# Yukari_3_11DoF_2.net
KiCad netlist of a schematic drawn in EAGLE
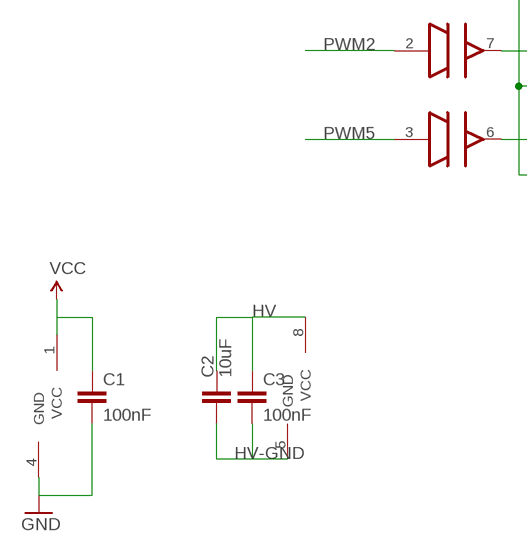
[diagram p0: schematic, sheet 1, part 1 of 2]
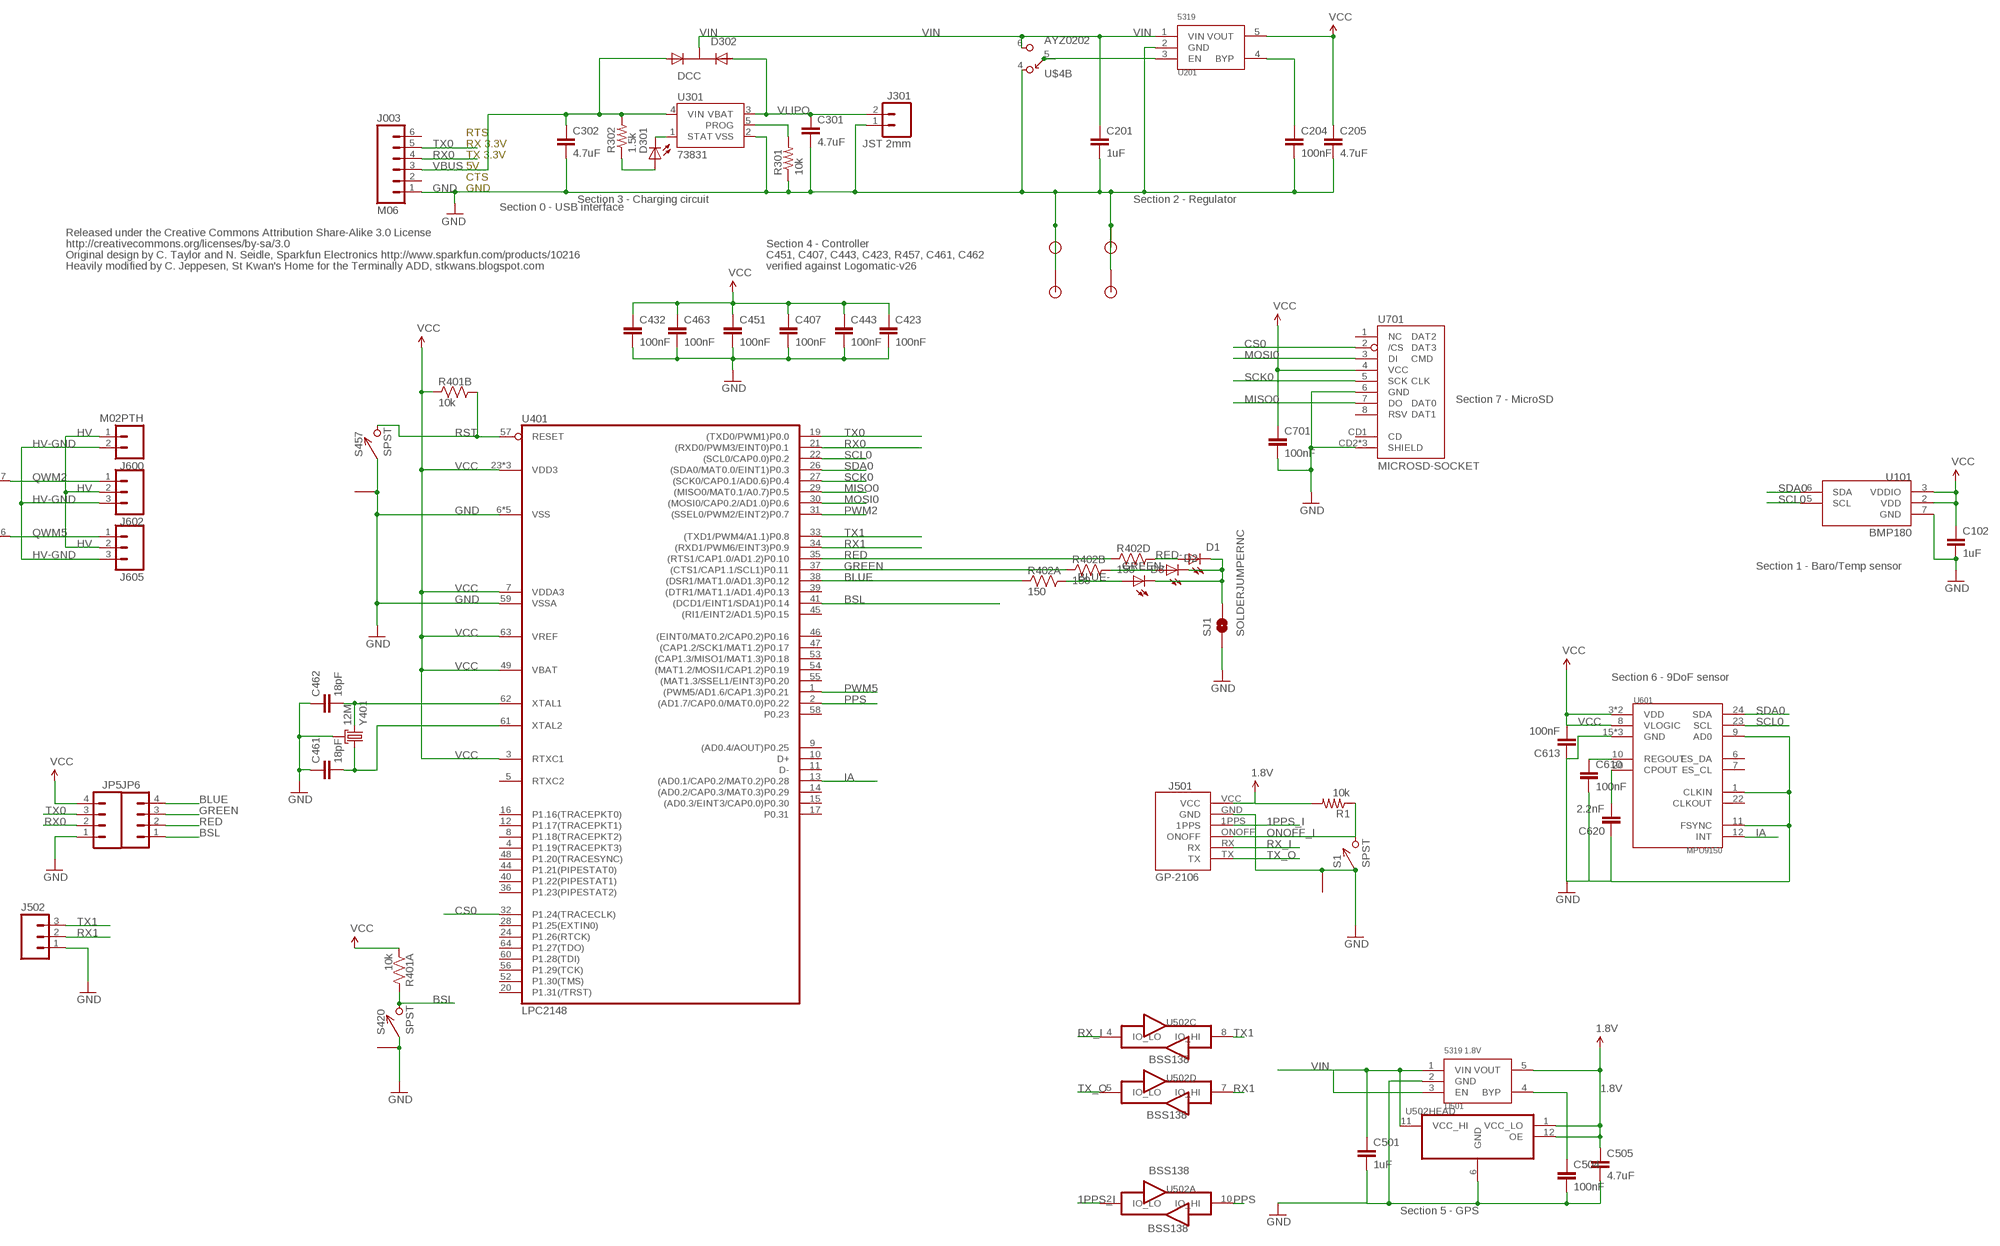
[diagram p1: schematic, sheet 1, part 2 of 2]

(export (version "E")
  (design (tool "Eeschema 10.0.6"))
  (components
    (comp (ref "C1")
      (value "100nF")
      (footprint "eagle-import:0402-CAP")
      (libsource (lib "eagle-import") (part "CAP0402-CAP"))
    )
    (comp (ref "C2")
      (value "10uF")
      (footprint "eagle-import:0603-CAP")
      (libsource (lib "eagle-import") (part "CAP0603-CAP"))
    )
    (comp (ref "C3")
      (value "100nF")
      (footprint "eagle-import:0402-CAP")
      (libsource (lib "eagle-import") (part "CAP0402-CAP"))
    )
    (comp (ref "C102")
      (value "1uF")
      (footprint "eagle-import:0402-CAP")
      (libsource (lib "eagle-import") (part "SparkFun-Passives_CAP0402-CAP"))
    )
    (comp (ref "C201")
      (value "1uF")
      (footprint "eagle-import:0402-CAP")
      (libsource (lib "eagle-import") (part "CAP0402-CAP"))
    )
    (comp (ref "C204")
      (value "100nF")
      (footprint "eagle-import:0402-CAP")
      (libsource (lib "eagle-import") (part "CAP0402-CAP"))
    )
    (comp (ref "C205")
      (value "4.7uF")
      (footprint "eagle-import:0402-CAP")
      (libsource (lib "eagle-import") (part "CAP0402-CAP"))
    )
    (comp (ref "C301")
      (value "4.7uF")
      (footprint "eagle-import:0402-CAP")
      (libsource (lib "eagle-import") (part "CAP0402-CAP"))
    )
    (comp (ref "C302")
      (value "4.7uF")
      (footprint "eagle-import:0402-CAP")
      (libsource (lib "eagle-import") (part "CAP0402-CAP"))
    )
    (comp (ref "C407")
      (value "100nF")
      (footprint "eagle-import:0402-CAP")
      (libsource (lib "eagle-import") (part "CAP0402-CAP"))
    )
    (comp (ref "C423")
      (value "100nF")
      (footprint "eagle-import:0402-CAP")
      (libsource (lib "eagle-import") (part "CAP0402-CAP"))
    )
    (comp (ref "C432")
      (value "100nF")
      (footprint "eagle-import:0402-CAP")
      (libsource (lib "eagle-import") (part "CAP0402-CAP"))
    )
    (comp (ref "C443")
      (value "100nF")
      (footprint "eagle-import:0402-CAP")
      (libsource (lib "eagle-import") (part "CAP0402-CAP"))
    )
    (comp (ref "C451")
      (value "100nF")
      (footprint "eagle-import:0402-CAP")
      (libsource (lib "eagle-import") (part "CAP0402-CAP"))
    )
    (comp (ref "C461")
      (value "18pF")
      (footprint "eagle-import:0402-CAP")
      (libsource (lib "eagle-import") (part "CAP0402-CAP"))
    )
    (comp (ref "C462")
      (value "18pF")
      (footprint "eagle-import:0402-CAP")
      (libsource (lib "eagle-import") (part "CAP0402-CAP"))
    )
    (comp (ref "C463")
      (value "100nF")
      (footprint "eagle-import:0402-CAP")
      (libsource (lib "eagle-import") (part "CAP0402-CAP"))
    )
    (comp (ref "C501")
      (value "1uF")
      (footprint "eagle-import:0402-CAP")
      (libsource (lib "eagle-import") (part "CAP0402-CAP"))
    )
    (comp (ref "C504")
      (value "100nF")
      (footprint "eagle-import:0402-CAP")
      (libsource (lib "eagle-import") (part "CAP0402-CAP"))
    )
    (comp (ref "C505")
      (value "4.7uF")
      (footprint "eagle-import:0402-CAP")
      (libsource (lib "eagle-import") (part "CAP0402-CAP"))
    )
    (comp (ref "C610")
      (value "100nF")
      (footprint "eagle-import:0402-CAP")
      (libsource (lib "eagle-import") (part "SparkFun-Passives_CAP0402-CAP"))
    )
    (comp (ref "C613")
      (value "100nF")
      (footprint "eagle-import:0402-CAP")
      (libsource (lib "eagle-import") (part "SparkFun-Passives_CAP0402-CAP"))
    )
    (comp (ref "C620")
      (value "2.2nF")
      (footprint "eagle-import:0402-CAP")
      (libsource (lib "eagle-import") (part "SparkFun-Passives_CAP0402-CAP"))
    )
    (comp (ref "C701")
      (value "100nF")
      (footprint "eagle-import:0402-CAP")
      (libsource (lib "eagle-import") (part "CAP0402-CAP"))
    )
    (comp (ref "D1")
      (value "RED")
      (footprint "eagle-import:LED-0603")
      (libsource (lib "eagle-import") (part "LED0603"))
    )
    (comp (ref "D2")
      (value "GREEN")
      (footprint "eagle-import:LED-0603")
      (libsource (lib "eagle-import") (part "LED0603"))
    )
    (comp (ref "D3")
      (value "BLUE")
      (footprint "eagle-import:LED-0603")
      (libsource (lib "eagle-import") (part "LED0603"))
    )
    (comp (ref "D301")
      (value "RED")
      (footprint "eagle-import:LED-0603")
      (libsource (lib "eagle-import") (part "LED0603"))
    )
    (comp (ref "D302")
      (value "DCC")
      (footprint "eagle-import:SOT-23-3")
      (libsource (lib "eagle-import") (part "PMEG2005CT"))
    )
    (comp (ref "J003")
      (value "M06")
      (footprint "eagle-import:1X06")
      (libsource (lib "eagle-import") (part "M06SIP"))
    )
    (comp (ref "J301")
      (value "JST 2mm")
      (footprint "eagle-import:JST-2-SMD")
      (libsource (lib "eagle-import") (part "M02-JST-2MM-SMT"))
    )
    (comp (ref "J501")
      (value "GP-2106")
      (footprint "eagle-import:GP-2106")
      (libsource (lib "eagle-import") (part "GP-2106"))
    )
    (comp (ref "J502")
      (value "M03PTH")
      (footprint "eagle-import:1X03")
      (libsource (lib "eagle-import") (part "M03PTH"))
    )
    (comp (ref "J600")
      (value "M02PTH")
      (footprint "eagle-import:1X02")
      (libsource (lib "eagle-import") (part "SparkFun-Connectors_M02PTH"))
    )
    (comp (ref "J602")
      (value "M03PTH")
      (footprint "eagle-import:1X03")
      (libsource (lib "eagle-import") (part "M03PTH"))
    )
    (comp (ref "J605")
      (value "M03PTH")
      (footprint "eagle-import:1X03")
      (libsource (lib "eagle-import") (part "M03PTH"))
    )
    (comp (ref "JP1")
      (value "STANDOFF")
      (footprint "eagle-import:STANDOFF")
      (libsource (lib "eagle-import") (part "STANDOFF"))
    )
    (comp (ref "JP2")
      (value "STANDOFF")
      (footprint "eagle-import:STANDOFF")
      (libsource (lib "eagle-import") (part "STANDOFF"))
    )
    (comp (ref "JP3")
      (value "STANDOFF")
      (footprint "eagle-import:STANDOFF")
      (libsource (lib "eagle-import") (part "STANDOFF"))
    )
    (comp (ref "JP4")
      (value "STANDOFF")
      (footprint "eagle-import:STANDOFF")
      (libsource (lib "eagle-import") (part "STANDOFF"))
    )
    (comp (ref "JP5")
      (value "M04PTH")
      (footprint "eagle-import:1X04")
      (libsource (lib "eagle-import") (part "M04PTH"))
    )
    (comp (ref "JP6")
      (value "M04PTH")
      (footprint "eagle-import:1X04")
      (libsource (lib "eagle-import") (part "M04PTH"))
    )
    (comp (ref "R1")
      (value "10k")
      (footprint "eagle-import:0402-RES")
      (libsource (lib "eagle-import") (part "RESISTOR0402-RES"))
    )
    (comp (ref "R301")
      (value "10k")
      (footprint "eagle-import:0402-RES")
      (libsource (lib "eagle-import") (part "RESISTOR0402-RES"))
    )
    (comp (ref "R302")
      (value "1.5k")
      (footprint "eagle-import:0402-RES")
      (libsource (lib "eagle-import") (part "RESISTOR0402-RES"))
    )
    (comp (ref "R401")
      (value "10k")
      (footprint "eagle-import:CRA02")
      (libsource (lib "eagle-import") (part "RP2EXB24V"))
    )
    (comp (ref "R402")
      (value "150")
      (footprint "eagle-import:CRA04")
      (libsource (lib "eagle-import") (part "RP404"))
    )
    (comp (ref "S1")
      (value "SPST")
      (footprint "eagle-import:B3U-1100P")
      (libsource (lib "eagle-import") (part "B3U-1100P"))
    )
    (comp (ref "S420")
      (value "SPST")
      (footprint "eagle-import:B3U-1100P")
      (libsource (lib "eagle-import") (part "B3U-1100P"))
    )
    (comp (ref "S457")
      (value "SPST")
      (footprint "eagle-import:B3U-1100P")
      (libsource (lib "eagle-import") (part "B3U-1100P"))
    )
    (comp (ref "SJ1")
      (value "SOLDERJUMPERNC")
      (footprint "eagle-import:SJ_2S")
      (libsource (lib "eagle-import") (part "SOLDERJUMPERNC"))
    )
    (comp (ref "U$4")
      (value "AYZ0202")
      (footprint "eagle-import:AYZ0202")
      (libsource (lib "eagle-import") (part "AYZ0202"))
    )
    (comp (ref "U101")
      (value "BMP180")
      (footprint "eagle-import:BMP180")
      (libsource (lib "eagle-import") (part "BMP180"))
    )
    (comp (ref "U201")
      (value "5319")
      (footprint "eagle-import:SOT-23-5")
      (libsource (lib "eagle-import") (part "MIC5319D5"))
    )
    (comp (ref "U301")
      (value "73831")
      (footprint "eagle-import:SOT23-5")
      (libsource (lib "eagle-import") (part "MCP73831"))
    )
    (comp (ref "U401")
      (value "LPC2148")
      (footprint "eagle-import:LQFP64")
      (libsource (lib "eagle-import") (part "LPC2148"))
    )
    (comp (ref "U501")
      (value "5319 1.8V")
      (footprint "eagle-import:SOT-23-5")
      (libsource (lib "eagle-import") (part "MIC5319D5"))
    )
    (comp (ref "U502")
      (value "TXB0104RUT")
      (footprint "eagle-import:R-PUQFN-N12")
      (libsource (lib "eagle-import") (part "TXB0104RUT"))
    )
    (comp (ref "U600")
      (value "ADUM3221")
      (footprint "eagle-import:SO8N")
      (libsource (lib "eagle-import") (part "ADUM3221"))
    )
    (comp (ref "U601")
      (value "MPU9150")
      (footprint "eagle-import:LLGA24")
      (libsource (lib "eagle-import") (part "MPU9150"))
    )
    (comp (ref "U701")
      (value "MICROSD-SOCKET")
      (footprint "eagle-import:MICROSD-SOCKET-PP")
      (libsource (lib "eagle-import") (part "MICROSD-SOCKET"))
    )
    (comp (ref "Y401")
      (value "12M")
      (footprint "eagle-import:CRYSTAL_SMD")
      (libsource (lib "eagle-import") (part "TSX-3225"))
    )
  )
  (nets
    (net (code "1") (name "/1PPS_I") (class "Default")
      (node (ref "J501") (pin "1PPS") (pinfunction "1PPS_1PPS") (pintype "bidirectional"))
      (node (ref "U502") (pin "2") (pinfunction "IO_LO_2") (pintype "bidirectional"))
    )
    (net (code "2") (name "/BLUE") (class "Default")
      (node (ref "JP6") (pin "4") (pinfunction "4_4") (pintype "passive"))
      (node (ref "R402") (pin "1") (pinfunction "1_1") (pintype "passive"))
      (node (ref "U401") (pin "38") (pinfunction "(DSR1/MAT1.0/AD1.3)P0.12_38") (pintype "bidirectional"))
    )
    (net (code "3") (name "/BLUE-") (class "Default")
      (node (ref "D3") (pin "A") (pinfunction "A_A") (pintype "passive"))
      (node (ref "R402") (pin "8") (pinfunction "2_8") (pintype "passive"))
    )
    (net (code "4") (name "/BSL") (class "Default")
      (node (ref "JP6") (pin "1") (pinfunction "1_1") (pintype "passive"))
      (node (ref "R401") (pin "4") (pinfunction "2_4") (pintype "passive"))
      (node (ref "S420") (pin "P$2") (pinfunction "2_P$2") (pintype "bidirectional"))
      (node (ref "U401") (pin "41") (pinfunction "(DCD1/EINT1/SDA1)P0.14_41") (pintype "bidirectional"))
    )
    (net (code "5") (name "/CS0") (class "Default")
      (node (ref "U401") (pin "32") (pinfunction "P1.24(TRACECLK)_32") (pintype "bidirectional"))
      (node (ref "U701") (pin "2") (pinfunction "/CS_2") (pintype "bidirectional"))
    )
    (net (code "6") (name "/GREEN") (class "Default")
      (node (ref "JP6") (pin "3") (pinfunction "3_3") (pintype "passive"))
      (node (ref "R402") (pin "2") (pinfunction "1_2") (pintype "passive"))
      (node (ref "U401") (pin "37") (pinfunction "(CTS1/CAP1.1/SCL1)P0.11_37") (pintype "bidirectional"))
    )
    (net (code "7") (name "/GREEN-") (class "Default")
      (node (ref "D2") (pin "A") (pinfunction "A_A") (pintype "passive"))
      (node (ref "R402") (pin "7") (pinfunction "2_7") (pintype "passive"))
    )
    (net (code "8") (name "/HV") (class "Default")
      (node (ref "C2") (pin "1") (pinfunction "1_1") (pintype "passive"))
      (node (ref "C3") (pin "1") (pinfunction "1_1") (pintype "passive"))
      (node (ref "J600") (pin "1") (pinfunction "1_1") (pintype "passive"))
      (node (ref "J602") (pin "2") (pinfunction "2_2") (pintype "passive"))
      (node (ref "J605") (pin "2") (pinfunction "2_2") (pintype "passive"))
      (node (ref "U600") (pin "8") (pinfunction "VCC_8") (pintype "bidirectional"))
    )
    (net (code "9") (name "/HV-GND") (class "Default")
      (node (ref "C2") (pin "2") (pinfunction "2_2") (pintype "passive"))
      (node (ref "C3") (pin "2") (pinfunction "2_2") (pintype "passive"))
      (node (ref "J600") (pin "2") (pinfunction "2_2") (pintype "passive"))
      (node (ref "J602") (pin "3") (pinfunction "3_3") (pintype "passive"))
      (node (ref "J605") (pin "3") (pinfunction "3_3") (pintype "passive"))
      (node (ref "U600") (pin "5") (pinfunction "GND_5") (pintype "bidirectional"))
    )
    (net (code "10") (name "/IA") (class "Default")
      (node (ref "U401") (pin "13") (pinfunction "(AD0.1/CAP0.2/MAT0.2)P0.28_13") (pintype "bidirectional"))
      (node (ref "U601") (pin "12") (pinfunction "INT_12") (pintype "bidirectional"))
    )
    (net (code "11") (name "/MISO0") (class "Default")
      (node (ref "U401") (pin "29") (pinfunction "(MISO0/MAT0.1/A0.7)P0.5_29") (pintype "bidirectional"))
      (node (ref "U701") (pin "7") (pinfunction "DO_7") (pintype "bidirectional"))
    )
    (net (code "12") (name "/MOSI0") (class "Default")
      (node (ref "U401") (pin "30") (pinfunction "(MOSI0/CAP0.2/AD1.0)P0.6_30") (pintype "bidirectional"))
      (node (ref "U701") (pin "3") (pinfunction "DI_3") (pintype "bidirectional"))
    )
    (net (code "13") (name "/ONOFF_I") (class "Default")
      (node (ref "J501") (pin "ONOFF") (pinfunction "ONOFF_ONOFF") (pintype "bidirectional"))
      (node (ref "R1") (pin "1") (pinfunction "1_1") (pintype "passive"))
      (node (ref "S1") (pin "P$2") (pinfunction "2_P$2") (pintype "bidirectional"))
    )
    (net (code "14") (name "/PPS") (class "Default")
      (node (ref "U401") (pin "2") (pinfunction "(AD1.7/CAP0.0/MAT0.0)P0.22_2") (pintype "bidirectional"))
      (node (ref "U502") (pin "10") (pinfunction "IO_HI_10") (pintype "bidirectional"))
    )
    (net (code "15") (name "/PWM2") (class "Default")
      (node (ref "U401") (pin "31") (pinfunction "(SSEL0/PWM2/EINT2)P0.7_31") (pintype "bidirectional"))
      (node (ref "U600") (pin "2") (pinfunction "IN_2") (pintype "input"))
    )
    (net (code "16") (name "/PWM5") (class "Default")
      (node (ref "U401") (pin "1") (pinfunction "(PWM5/AD1.6/CAP1.3)P0.21_1") (pintype "bidirectional"))
      (node (ref "U600") (pin "3") (pinfunction "IN_3") (pintype "input"))
    )
    (net (code "17") (name "/QWM2") (class "Default")
      (node (ref "J602") (pin "1") (pinfunction "1_1") (pintype "passive"))
      (node (ref "U600") (pin "7") (pinfunction "OUT_7") (pintype "bidirectional"))
    )
    (net (code "18") (name "/QWM5") (class "Default")
      (node (ref "J605") (pin "1") (pinfunction "1_1") (pintype "passive"))
      (node (ref "U600") (pin "6") (pinfunction "OUT_6") (pintype "bidirectional"))
    )
    (net (code "19") (name "/RED") (class "Default")
      (node (ref "JP6") (pin "2") (pinfunction "2_2") (pintype "passive"))
      (node (ref "R402") (pin "4") (pinfunction "1_4") (pintype "passive"))
      (node (ref "U401") (pin "35") (pinfunction "(RTS1/CAP1.0/AD1.2)P0.10_35") (pintype "bidirectional"))
    )
    (net (code "20") (name "/RED-") (class "Default")
      (node (ref "D1") (pin "A") (pinfunction "A_A") (pintype "passive"))
      (node (ref "R402") (pin "5") (pinfunction "2_5") (pintype "passive"))
    )
    (net (code "21") (name "/RST") (class "Default")
      (node (ref "R401") (pin "3") (pinfunction "2_3") (pintype "passive"))
      (node (ref "S457") (pin "P$2") (pinfunction "2_P$2") (pintype "bidirectional"))
      (node (ref "U401") (pin "57") (pinfunction "RESET_57") (pintype "input"))
    )
    (net (code "22") (name "/RX0") (class "Default")
      (node (ref "J003") (pin "4") (pinfunction "4_4") (pintype "passive"))
      (node (ref "JP5") (pin "2") (pinfunction "2_2") (pintype "passive"))
      (node (ref "U401") (pin "21") (pinfunction "(RXD0/PWM3/EINT0)P0.1_21") (pintype "bidirectional"))
    )
    (net (code "23") (name "/RX1") (class "Default")
      (node (ref "J502") (pin "2") (pinfunction "2_2") (pintype "passive"))
      (node (ref "U401") (pin "34") (pinfunction "(RXD1/PWM6/EINT3)P0.9_34") (pintype "bidirectional"))
      (node (ref "U502") (pin "7") (pinfunction "IO_HI_7") (pintype "bidirectional"))
    )
    (net (code "24") (name "/RX_I") (class "Default")
      (node (ref "J501") (pin "RX") (pinfunction "RX_RX") (pintype "bidirectional"))
      (node (ref "U502") (pin "4") (pinfunction "IO_LO_4") (pintype "bidirectional"))
    )
    (net (code "25") (name "/SCK0") (class "Default")
      (node (ref "U401") (pin "27") (pinfunction "(SCK0/CAP0.1/AD0.6)P0.4_27") (pintype "bidirectional"))
      (node (ref "U701") (pin "5") (pinfunction "SCK_5") (pintype "bidirectional"))
    )
    (net (code "26") (name "/SCL0") (class "Default")
      (node (ref "U101") (pin "5") (pinfunction "SCL_5") (pintype "input"))
      (node (ref "U401") (pin "22") (pinfunction "(SCL0/CAP0.0)P0.2_22") (pintype "bidirectional"))
      (node (ref "U601") (pin "23") (pinfunction "SCL_23") (pintype "bidirectional"))
    )
    (net (code "27") (name "/SDA0") (class "Default")
      (node (ref "U101") (pin "6") (pinfunction "SDA_6") (pintype "bidirectional"))
      (node (ref "U401") (pin "26") (pinfunction "(SDA0/MAT0.0/EINT1)P0.3_26") (pintype "bidirectional"))
      (node (ref "U601") (pin "24") (pinfunction "SDA_24") (pintype "bidirectional"))
    )
    (net (code "28") (name "/TX0") (class "Default")
      (node (ref "J003") (pin "5") (pinfunction "5_5") (pintype "passive"))
      (node (ref "JP5") (pin "3") (pinfunction "3_3") (pintype "passive"))
      (node (ref "U401") (pin "19") (pinfunction "(TXD0/PWM1)P0.0_19") (pintype "bidirectional"))
    )
    (net (code "29") (name "/TX1") (class "Default")
      (node (ref "J502") (pin "3") (pinfunction "3_3") (pintype "passive"))
      (node (ref "U401") (pin "33") (pinfunction "(TXD1/PWM4/A1.1)P0.8_33") (pintype "bidirectional"))
      (node (ref "U502") (pin "8") (pinfunction "IO_HI_8") (pintype "bidirectional"))
    )
    (net (code "30") (name "/TX_O") (class "Default")
      (node (ref "J501") (pin "TX") (pinfunction "TX_TX") (pintype "bidirectional"))
      (node (ref "U502") (pin "5") (pinfunction "IO_LO_5") (pintype "bidirectional"))
    )
    (net (code "31") (name "/VBUS") (class "Default")
      (node (ref "C302") (pin "1") (pinfunction "1_1") (pintype "passive"))
      (node (ref "D302") (pin "1") (pinfunction "A1_1") (pintype "passive"))
      (node (ref "J003") (pin "3") (pinfunction "3_3") (pintype "passive"))
      (node (ref "R302") (pin "2") (pinfunction "2_2") (pintype "passive"))
      (node (ref "U301") (pin "4") (pinfunction "VIN_4") (pintype "power_in"))
    )
    (net (code "32") (name "/VIN") (class "Default")
      (node (ref "C201") (pin "1") (pinfunction "1_1") (pintype "passive"))
      (node (ref "C501") (pin "1") (pinfunction "1_1") (pintype "passive"))
      (node (ref "D302") (pin "3") (pinfunction "K_3") (pintype "passive"))
      (node (ref "U$4") (pin "6") (pinfunction "P$2_6") (pintype "bidirectional"))
      (node (ref "U201") (pin "1") (pinfunction "VIN_1") (pintype "bidirectional"))
      (node (ref "U501") (pin "1") (pinfunction "VIN_1") (pintype "bidirectional"))
      (node (ref "U501") (pin "3") (pinfunction "EN_3") (pintype "bidirectional"))
      (node (ref "U502") (pin "11") (pinfunction "VCC_HI_11") (pintype "power_in"))
    )
    (net (code "33") (name "/VLIPO") (class "Default")
      (node (ref "C301") (pin "1") (pinfunction "1_1") (pintype "passive"))
      (node (ref "D302") (pin "2") (pinfunction "A2_2") (pintype "passive"))
      (node (ref "J301") (pin "2") (pinfunction "2_2") (pintype "passive"))
      (node (ref "U301") (pin "3") (pinfunction "VBAT_3") (pintype "power_in"))
    )
    (net (code "34") (name "1.8V") (class "Default")
      (node (ref "C505") (pin "1") (pinfunction "1_1") (pintype "passive"))
      (node (ref "J501") (pin "VCC") (pinfunction "VCC_VCC") (pintype "bidirectional"))
      (node (ref "R1") (pin "2") (pinfunction "2_2") (pintype "passive"))
      (node (ref "U501") (pin "5") (pinfunction "VOUT_5") (pintype "bidirectional"))
      (node (ref "U502") (pin "1") (pinfunction "VCC_LO_1") (pintype "power_in"))
      (node (ref "U502") (pin "12") (pinfunction "OE_12") (pintype "bidirectional"))
    )
    (net (code "35") (name "GND") (class "Default")
      (node (ref "C1") (pin "2") (pinfunction "2_2") (pintype "passive"))
      (node (ref "C102") (pin "2") (pinfunction "2_2") (pintype "passive"))
      (node (ref "C201") (pin "2") (pinfunction "2_2") (pintype "passive"))
      (node (ref "C204") (pin "2") (pinfunction "2_2") (pintype "passive"))
      (node (ref "C205") (pin "2") (pinfunction "2_2") (pintype "passive"))
      (node (ref "C301") (pin "2") (pinfunction "2_2") (pintype "passive"))
      (node (ref "C302") (pin "2") (pinfunction "2_2") (pintype "passive"))
      (node (ref "C407") (pin "2") (pinfunction "2_2") (pintype "passive"))
      (node (ref "C423") (pin "2") (pinfunction "2_2") (pintype "passive"))
      (node (ref "C432") (pin "2") (pinfunction "2_2") (pintype "passive"))
      (node (ref "C443") (pin "2") (pinfunction "2_2") (pintype "passive"))
      (node (ref "C451") (pin "2") (pinfunction "2_2") (pintype "passive"))
      (node (ref "C461") (pin "1") (pinfunction "1_1") (pintype "passive"))
      (node (ref "C462") (pin "1") (pinfunction "1_1") (pintype "passive"))
      (node (ref "C463") (pin "2") (pinfunction "2_2") (pintype "passive"))
      (node (ref "C501") (pin "2") (pinfunction "2_2") (pintype "passive"))
      (node (ref "C504") (pin "2") (pinfunction "2_2") (pintype "passive"))
      (node (ref "C505") (pin "2") (pinfunction "2_2") (pintype "passive"))
      (node (ref "C610") (pin "2") (pinfunction "2_2") (pintype "passive"))
      (node (ref "C613") (pin "1") (pinfunction "1_1") (pintype "passive"))
      (node (ref "C620") (pin "1") (pinfunction "1_1") (pintype "passive"))
      (node (ref "C701") (pin "2") (pinfunction "2_2") (pintype "passive"))
      (node (ref "J003") (pin "1") (pinfunction "1_1") (pintype "passive"))
      (node (ref "J301") (pin "1") (pinfunction "1_1") (pintype "passive"))
      (node (ref "J501") (pin "GND") (pinfunction "GND_GND") (pintype "bidirectional"))
      (node (ref "J502") (pin "1") (pinfunction "1_1") (pintype "passive"))
      (node (ref "JP1") (pin "P$1") (pinfunction "P$1_P$1") (pintype "bidirectional"))
      (node (ref "JP2") (pin "P$1") (pinfunction "P$1_P$1") (pintype "bidirectional"))
      (node (ref "JP3") (pin "P$1") (pinfunction "P$1_P$1") (pintype "bidirectional"))
      (node (ref "JP4") (pin "P$1") (pinfunction "P$1_P$1") (pintype "bidirectional"))
      (node (ref "JP5") (pin "1") (pinfunction "1_1") (pintype "passive"))
      (node (ref "R301") (pin "1") (pinfunction "1_1") (pintype "passive"))
      (node (ref "S1") (pin "P$1") (pinfunction "1_P$1") (pintype "bidirectional"))
      (node (ref "S1") (pin "P$3") (pinfunction "1_P$3") (pintype "bidirectional"))
      (node (ref "S420") (pin "P$1") (pinfunction "1_P$1") (pintype "bidirectional"))
      (node (ref "S420") (pin "P$3") (pinfunction "1_P$3") (pintype "bidirectional"))
      (node (ref "S457") (pin "P$1") (pinfunction "1_P$1") (pintype "bidirectional"))
      (node (ref "S457") (pin "P$3") (pinfunction "1_P$3") (pintype "bidirectional"))
      (node (ref "SJ1") (pin "1") (pinfunction "1_1") (pintype "passive"))
      (node (ref "U$4") (pin "4") (pinfunction "P$1_4") (pintype "bidirectional"))
      (node (ref "U101") (pin "7") (pinfunction "GND_7") (pintype "power_in"))
      (node (ref "U201") (pin "2") (pinfunction "GND_2") (pintype "bidirectional"))
      (node (ref "U301") (pin "2") (pinfunction "VSS_2") (pintype "power_in"))
      (node (ref "U401") (pin "18") (pinfunction "VSS_18") (pintype "power_in"))
      (node (ref "U401") (pin "25") (pinfunction "VSS_25") (pintype "power_in"))
      (node (ref "U401") (pin "42") (pinfunction "VSS_42") (pintype "power_in"))
      (node (ref "U401") (pin "50") (pinfunction "VSS_50") (pintype "power_in"))
      (node (ref "U401") (pin "59") (pinfunction "VSSA_59") (pintype "power_in"))
      (node (ref "U401") (pin "6") (pinfunction "VSS_6") (pintype "power_in"))
      (node (ref "U501") (pin "2") (pinfunction "GND_2") (pintype "bidirectional"))
      (node (ref "U502") (pin "6") (pinfunction "GND_6") (pintype "power_in"))
      (node (ref "U600") (pin "4") (pinfunction "GND_4") (pintype "bidirectional"))
      (node (ref "U601") (pin "1") (pinfunction "CLKIN_1") (pintype "bidirectional"))
      (node (ref "U601") (pin "11") (pinfunction "FSYNC_11") (pintype "bidirectional"))
      (node (ref "U601") (pin "15") (pinfunction "GND_15") (pintype "bidirectional"))
      (node (ref "U601") (pin "17") (pinfunction "GND_17") (pintype "bidirectional"))
      (node (ref "U601") (pin "18") (pinfunction "GND_18") (pintype "bidirectional"))
      (node (ref "U601") (pin "9") (pinfunction "AD0_9") (pintype "bidirectional"))
      (node (ref "U701") (pin "6") (pinfunction "GND_6") (pintype "bidirectional"))
      (node (ref "U701") (pin "CD2") (pinfunction "SHIELD_CD2") (pintype "bidirectional"))
      (node (ref "U701") (pin "GND1") (pinfunction "SHIELD_GND1") (pintype "bidirectional"))
      (node (ref "U701") (pin "GND3") (pinfunction "SHIELD_GND3") (pintype "bidirectional"))
      (node (ref "Y401") (pin "2") (pinfunction "GND_2") (pintype "passive"))
      (node (ref "Y401") (pin "4") (pinfunction "GND_4") (pintype "passive"))
    )
    (net (code "36") (name "Net-(D1-PadC)") (class "Default")
      (node (ref "D1") (pin "C") (pinfunction "C_C") (pintype "passive"))
      (node (ref "D2") (pin "C") (pinfunction "C_C") (pintype "passive"))
      (node (ref "D3") (pin "C") (pinfunction "C_C") (pintype "passive"))
      (node (ref "SJ1") (pin "2") (pinfunction "2_2") (pintype "passive"))
    )
    (net (code "37") (name "Net-(D301-PadA)") (class "Default")
      (node (ref "D301") (pin "A") (pinfunction "A_A") (pintype "passive"))
      (node (ref "R302") (pin "1") (pinfunction "1_1") (pintype "passive"))
    )
    (net (code "38") (name "Net-(U$4B-P$3)") (class "Default")
      (node (ref "U$4") (pin "5") (pinfunction "P$3_5") (pintype "bidirectional"))
      (node (ref "U201") (pin "3") (pinfunction "EN_3") (pintype "bidirectional"))
    )
    (net (code "39") (name "Net-(U201-BYP)") (class "Default")
      (node (ref "C204") (pin "1") (pinfunction "1_1") (pintype "passive"))
      (node (ref "U201") (pin "4") (pinfunction "BYP_4") (pintype "bidirectional"))
    )
    (net (code "40") (name "Net-(U301-PROG)") (class "Default")
      (node (ref "R301") (pin "2") (pinfunction "2_2") (pintype "passive"))
      (node (ref "U301") (pin "5") (pinfunction "PROG_5") (pintype "input"))
    )
    (net (code "41") (name "Net-(U301-STAT)") (class "Default")
      (node (ref "D301") (pin "C") (pinfunction "C_C") (pintype "passive"))
      (node (ref "U301") (pin "1") (pinfunction "STAT_1") (pintype "output"))
    )
    (net (code "42") (name "Net-(U401-XTAL1)") (class "Default")
      (node (ref "C462") (pin "2") (pinfunction "2_2") (pintype "passive"))
      (node (ref "U401") (pin "62") (pinfunction "XTAL1_62") (pintype "input"))
      (node (ref "Y401") (pin "3") (pinfunction "2_3") (pintype "passive"))
    )
    (net (code "43") (name "Net-(U401-XTAL2)") (class "Default")
      (node (ref "C461") (pin "2") (pinfunction "2_2") (pintype "passive"))
      (node (ref "U401") (pin "61") (pinfunction "XTAL2_61") (pintype "output"))
      (node (ref "Y401") (pin "1") (pinfunction "1_1") (pintype "passive"))
    )
    (net (code "44") (name "Net-(U501-BYP)") (class "Default")
      (node (ref "C504") (pin "1") (pinfunction "1_1") (pintype "passive"))
      (node (ref "U501") (pin "4") (pinfunction "BYP_4") (pintype "bidirectional"))
    )
    (net (code "45") (name "Net-(U601-CPOUT)") (class "Default")
      (node (ref "C620") (pin "2") (pinfunction "2_2") (pintype "passive"))
      (node (ref "U601") (pin "20") (pinfunction "CPOUT_20") (pintype "bidirectional"))
    )
    (net (code "46") (name "Net-(U601-REGOUT)") (class "Default")
      (node (ref "C610") (pin "1") (pinfunction "1_1") (pintype "passive"))
      (node (ref "U601") (pin "10") (pinfunction "REGOUT_10") (pintype "bidirectional"))
    )
    (net (code "47") (name "VCC") (class "Default")
      (node (ref "C1") (pin "1") (pinfunction "1_1") (pintype "passive"))
      (node (ref "C102") (pin "1") (pinfunction "1_1") (pintype "passive"))
      (node (ref "C205") (pin "1") (pinfunction "1_1") (pintype "passive"))
      (node (ref "C407") (pin "1") (pinfunction "1_1") (pintype "passive"))
      (node (ref "C423") (pin "1") (pinfunction "1_1") (pintype "passive"))
      (node (ref "C432") (pin "1") (pinfunction "1_1") (pintype "passive"))
      (node (ref "C443") (pin "1") (pinfunction "1_1") (pintype "passive"))
      (node (ref "C451") (pin "1") (pinfunction "1_1") (pintype "passive"))
      (node (ref "C463") (pin "1") (pinfunction "1_1") (pintype "passive"))
      (node (ref "C613") (pin "2") (pinfunction "2_2") (pintype "passive"))
      (node (ref "C701") (pin "1") (pinfunction "1_1") (pintype "passive"))
      (node (ref "JP5") (pin "4") (pinfunction "4_4") (pintype "passive"))
      (node (ref "R401") (pin "1") (pinfunction "1_1") (pintype "passive"))
      (node (ref "R401") (pin "2") (pinfunction "1_2") (pintype "passive"))
      (node (ref "U101") (pin "2") (pinfunction "VDD_2") (pintype "power_in"))
      (node (ref "U101") (pin "3") (pinfunction "VDDIO_3") (pintype "power_in"))
      (node (ref "U201") (pin "5") (pinfunction "VOUT_5") (pintype "bidirectional"))
      (node (ref "U401") (pin "23") (pinfunction "VDD3_23") (pintype "power_in"))
      (node (ref "U401") (pin "3") (pinfunction "RTXC1_3") (pintype "input"))
      (node (ref "U401") (pin "43") (pinfunction "VDD3_43") (pintype "power_in"))
      (node (ref "U401") (pin "49") (pinfunction "VBAT_49") (pintype "power_in"))
      (node (ref "U401") (pin "51") (pinfunction "VDD3_51") (pintype "power_in"))
      (node (ref "U401") (pin "63") (pinfunction "VREF_63") (pintype "input"))
      (node (ref "U401") (pin "7") (pinfunction "VDDA3_7") (pintype "power_in"))
      (node (ref "U600") (pin "1") (pinfunction "VCC_1") (pintype "bidirectional"))
      (node (ref "U601") (pin "13") (pinfunction "VDD_13") (pintype "bidirectional"))
      (node (ref "U601") (pin "3") (pinfunction "VDD_3") (pintype "bidirectional"))
      (node (ref "U601") (pin "8") (pinfunction "VLOGIC_8") (pintype "bidirectional"))
      (node (ref "U701") (pin "4") (pinfunction "VCC_4") (pintype "bidirectional"))
    )
    (net (code "48") (name "unconnected-(J003-Pad2)") (class "Default")
      (node (ref "J003") (pin "2") (pinfunction "2_2") (pintype "passive"))
    )
    (net (code "49") (name "unconnected-(J003-Pad6)") (class "Default")
      (node (ref "J003") (pin "6") (pinfunction "6_6") (pintype "passive"))
    )
    (net (code "50") (name "unconnected-(U401-(AD0.2{slash}CAP0.3{slash}MAT0.3)P0.29-Pad14)") (class "Default")
      (node (ref "U401") (pin "14") (pinfunction "(AD0.2/CAP0.3/MAT0.3)P0.29_14") (pintype "bidirectional"))
    )
    (net (code "51") (name "unconnected-(U401-(AD0.3{slash}EINT3{slash}CAP0.0)P0.30-Pad15)") (class "Default")
      (node (ref "U401") (pin "15") (pinfunction "(AD0.3/EINT3/CAP0.0)P0.30_15") (pintype "bidirectional"))
    )
    (net (code "52") (name "unconnected-(U401-(AD0.4{slash}AOUT)P0.25-Pad9)") (class "Default")
      (node (ref "U401") (pin "9") (pinfunction "(AD0.4/AOUT)P0.25_9") (pintype "bidirectional"))
    )
    (net (code "53") (name "unconnected-(U401-(CAP1.2{slash}SCK1{slash}MAT1.2)P0.17-Pad47)") (class "Default")
      (node (ref "U401") (pin "47") (pinfunction "(CAP1.2/SCK1/MAT1.2)P0.17_47") (pintype "bidirectional"))
    )
    (net (code "54") (name "unconnected-(U401-(CAP1.3{slash}MISO1{slash}MAT1.3)P0.18-Pad53)") (class "Default")
      (node (ref "U401") (pin "53") (pinfunction "(CAP1.3/MISO1/MAT1.3)P0.18_53") (pintype "bidirectional"))
    )
    (net (code "55") (name "unconnected-(U401-(DTR1{slash}MAT1.1{slash}AD1.4)P0.13-Pad39)") (class "Default")
      (node (ref "U401") (pin "39") (pinfunction "(DTR1/MAT1.1/AD1.4)P0.13_39") (pintype "bidirectional"))
    )
    (net (code "56") (name "unconnected-(U401-(EINT0{slash}MAT0.2{slash}CAP0.2)P0.16-Pad46)") (class "Default")
      (node (ref "U401") (pin "46") (pinfunction "(EINT0/MAT0.2/CAP0.2)P0.16_46") (pintype "bidirectional"))
    )
    (net (code "57") (name "unconnected-(U401-(MAT1.2{slash}MOSI1{slash}CAP1.2)P0.19-Pad54)") (class "Default")
      (node (ref "U401") (pin "54") (pinfunction "(MAT1.2/MOSI1/CAP1.2)P0.19_54") (pintype "bidirectional"))
    )
    (net (code "58") (name "unconnected-(U401-(MAT1.3{slash}SSEL1{slash}EINT3)P0.20-Pad55)") (class "Default")
      (node (ref "U401") (pin "55") (pinfunction "(MAT1.3/SSEL1/EINT3)P0.20_55") (pintype "bidirectional"))
    )
    (net (code "59") (name "unconnected-(U401-(RI1{slash}EINT2{slash}AD1.5)P0.15-Pad45)") (class "Default")
      (node (ref "U401") (pin "45") (pinfunction "(RI1/EINT2/AD1.5)P0.15_45") (pintype "bidirectional"))
    )
    (net (code "60") (name "unconnected-(U401-D+-Pad10)") (class "Default")
      (node (ref "U401") (pin "10") (pinfunction "D+_10") (pintype "bidirectional"))
    )
    (net (code "61") (name "unconnected-(U401-D--Pad11)") (class "Default")
      (node (ref "U401") (pin "11") (pinfunction "D-_11") (pintype "bidirectional"))
    )
    (net (code "62") (name "unconnected-(U401-P0.23-Pad58)") (class "Default")
      (node (ref "U401") (pin "58") (pinfunction "P0.23_58") (pintype "bidirectional"))
    )
    (net (code "63") (name "unconnected-(U401-P0.31-Pad17)") (class "Default")
      (node (ref "U401") (pin "17") (pinfunction "P0.31_17") (pintype "output"))
    )
    (net (code "64") (name "unconnected-(U401-P1.16(TRACEPKT0)-Pad16)") (class "Default")
      (node (ref "U401") (pin "16") (pinfunction "P1.16(TRACEPKT0)_16") (pintype "bidirectional"))
    )
    (net (code "65") (name "unconnected-(U401-P1.17(TRACEPKT1)-Pad12)") (class "Default")
      (node (ref "U401") (pin "12") (pinfunction "P1.17(TRACEPKT1)_12") (pintype "bidirectional"))
    )
    (net (code "66") (name "unconnected-(U401-P1.18(TRACEPKT2)-Pad8)") (class "Default")
      (node (ref "U401") (pin "8") (pinfunction "P1.18(TRACEPKT2)_8") (pintype "bidirectional"))
    )
    (net (code "67") (name "unconnected-(U401-P1.19(TRACEPKT3)-Pad4)") (class "Default")
      (node (ref "U401") (pin "4") (pinfunction "P1.19(TRACEPKT3)_4") (pintype "bidirectional"))
    )
    (net (code "68") (name "unconnected-(U401-P1.20(TRACESYNC)-Pad48)") (class "Default")
      (node (ref "U401") (pin "48") (pinfunction "P1.20(TRACESYNC)_48") (pintype "bidirectional"))
    )
    (net (code "69") (name "unconnected-(U401-P1.21(PIPESTAT0)-Pad44)") (class "Default")
      (node (ref "U401") (pin "44") (pinfunction "P1.21(PIPESTAT0)_44") (pintype "bidirectional"))
    )
    (net (code "70") (name "unconnected-(U401-P1.22(PIPESTAT1)-Pad40)") (class "Default")
      (node (ref "U401") (pin "40") (pinfunction "P1.22(PIPESTAT1)_40") (pintype "bidirectional"))
    )
    (net (code "71") (name "unconnected-(U401-P1.23(PIPESTAT2)-Pad36)") (class "Default")
      (node (ref "U401") (pin "36") (pinfunction "P1.23(PIPESTAT2)_36") (pintype "bidirectional"))
    )
    (net (code "72") (name "unconnected-(U401-P1.25(EXTIN0)-Pad28)") (class "Default")
      (node (ref "U401") (pin "28") (pinfunction "P1.25(EXTIN0)_28") (pintype "bidirectional"))
    )
    (net (code "73") (name "unconnected-(U401-P1.26(RTCK)-Pad24)") (class "Default")
      (node (ref "U401") (pin "24") (pinfunction "P1.26(RTCK)_24") (pintype "bidirectional"))
    )
    (net (code "74") (name "unconnected-(U401-P1.27(TDO)-Pad64)") (class "Default")
      (node (ref "U401") (pin "64") (pinfunction "P1.27(TDO)_64") (pintype "bidirectional"))
    )
    (net (code "75") (name "unconnected-(U401-P1.28(TDI)-Pad60)") (class "Default")
      (node (ref "U401") (pin "60") (pinfunction "P1.28(TDI)_60") (pintype "bidirectional"))
    )
    (net (code "76") (name "unconnected-(U401-P1.29(TCK)-Pad56)") (class "Default")
      (node (ref "U401") (pin "56") (pinfunction "P1.29(TCK)_56") (pintype "bidirectional"))
    )
    (net (code "77") (name "unconnected-(U401-P1.30(TMS)-Pad52)") (class "Default")
      (node (ref "U401") (pin "52") (pinfunction "P1.30(TMS)_52") (pintype "bidirectional"))
    )
    (net (code "78") (name "unconnected-(U401-P1.31({slash}TRST)-Pad20)") (class "Default")
      (node (ref "U401") (pin "20") (pinfunction "P1.31(/TRST)_20") (pintype "bidirectional"))
    )
    (net (code "79") (name "unconnected-(U401-RTXC2-Pad5)") (class "Default")
      (node (ref "U401") (pin "5") (pinfunction "RTXC2_5") (pintype "output"))
    )
    (net (code "80") (name "unconnected-(U601-CLKOUT-Pad22)") (class "Default")
      (node (ref "U601") (pin "22") (pinfunction "CLKOUT_22") (pintype "bidirectional"))
    )
    (net (code "81") (name "unconnected-(U601-ES_CL-Pad7)") (class "Default")
      (node (ref "U601") (pin "7") (pinfunction "ES_CL_7") (pintype "bidirectional"))
    )
    (net (code "82") (name "unconnected-(U601-ES_DA-Pad6)") (class "Default")
      (node (ref "U601") (pin "6") (pinfunction "ES_DA_6") (pintype "bidirectional"))
    )
    (net (code "83") (name "unconnected-(U701-CD-PadCD1)") (class "Default")
      (node (ref "U701") (pin "CD1") (pinfunction "CD_CD1") (pintype "bidirectional"))
    )
    (net (code "84") (name "unconnected-(U701-NC-Pad1)") (class "Default")
      (node (ref "U701") (pin "1") (pinfunction "NC_1") (pintype "bidirectional"))
    )
    (net (code "85") (name "unconnected-(U701-RSV-Pad8)") (class "Default")
      (node (ref "U701") (pin "8") (pinfunction "RSV_8") (pintype "bidirectional"))
    )
  )
)
